# SCH_breakout_2024-04-23.net
KiCad netlist of a schematic drawn in EasyEDA
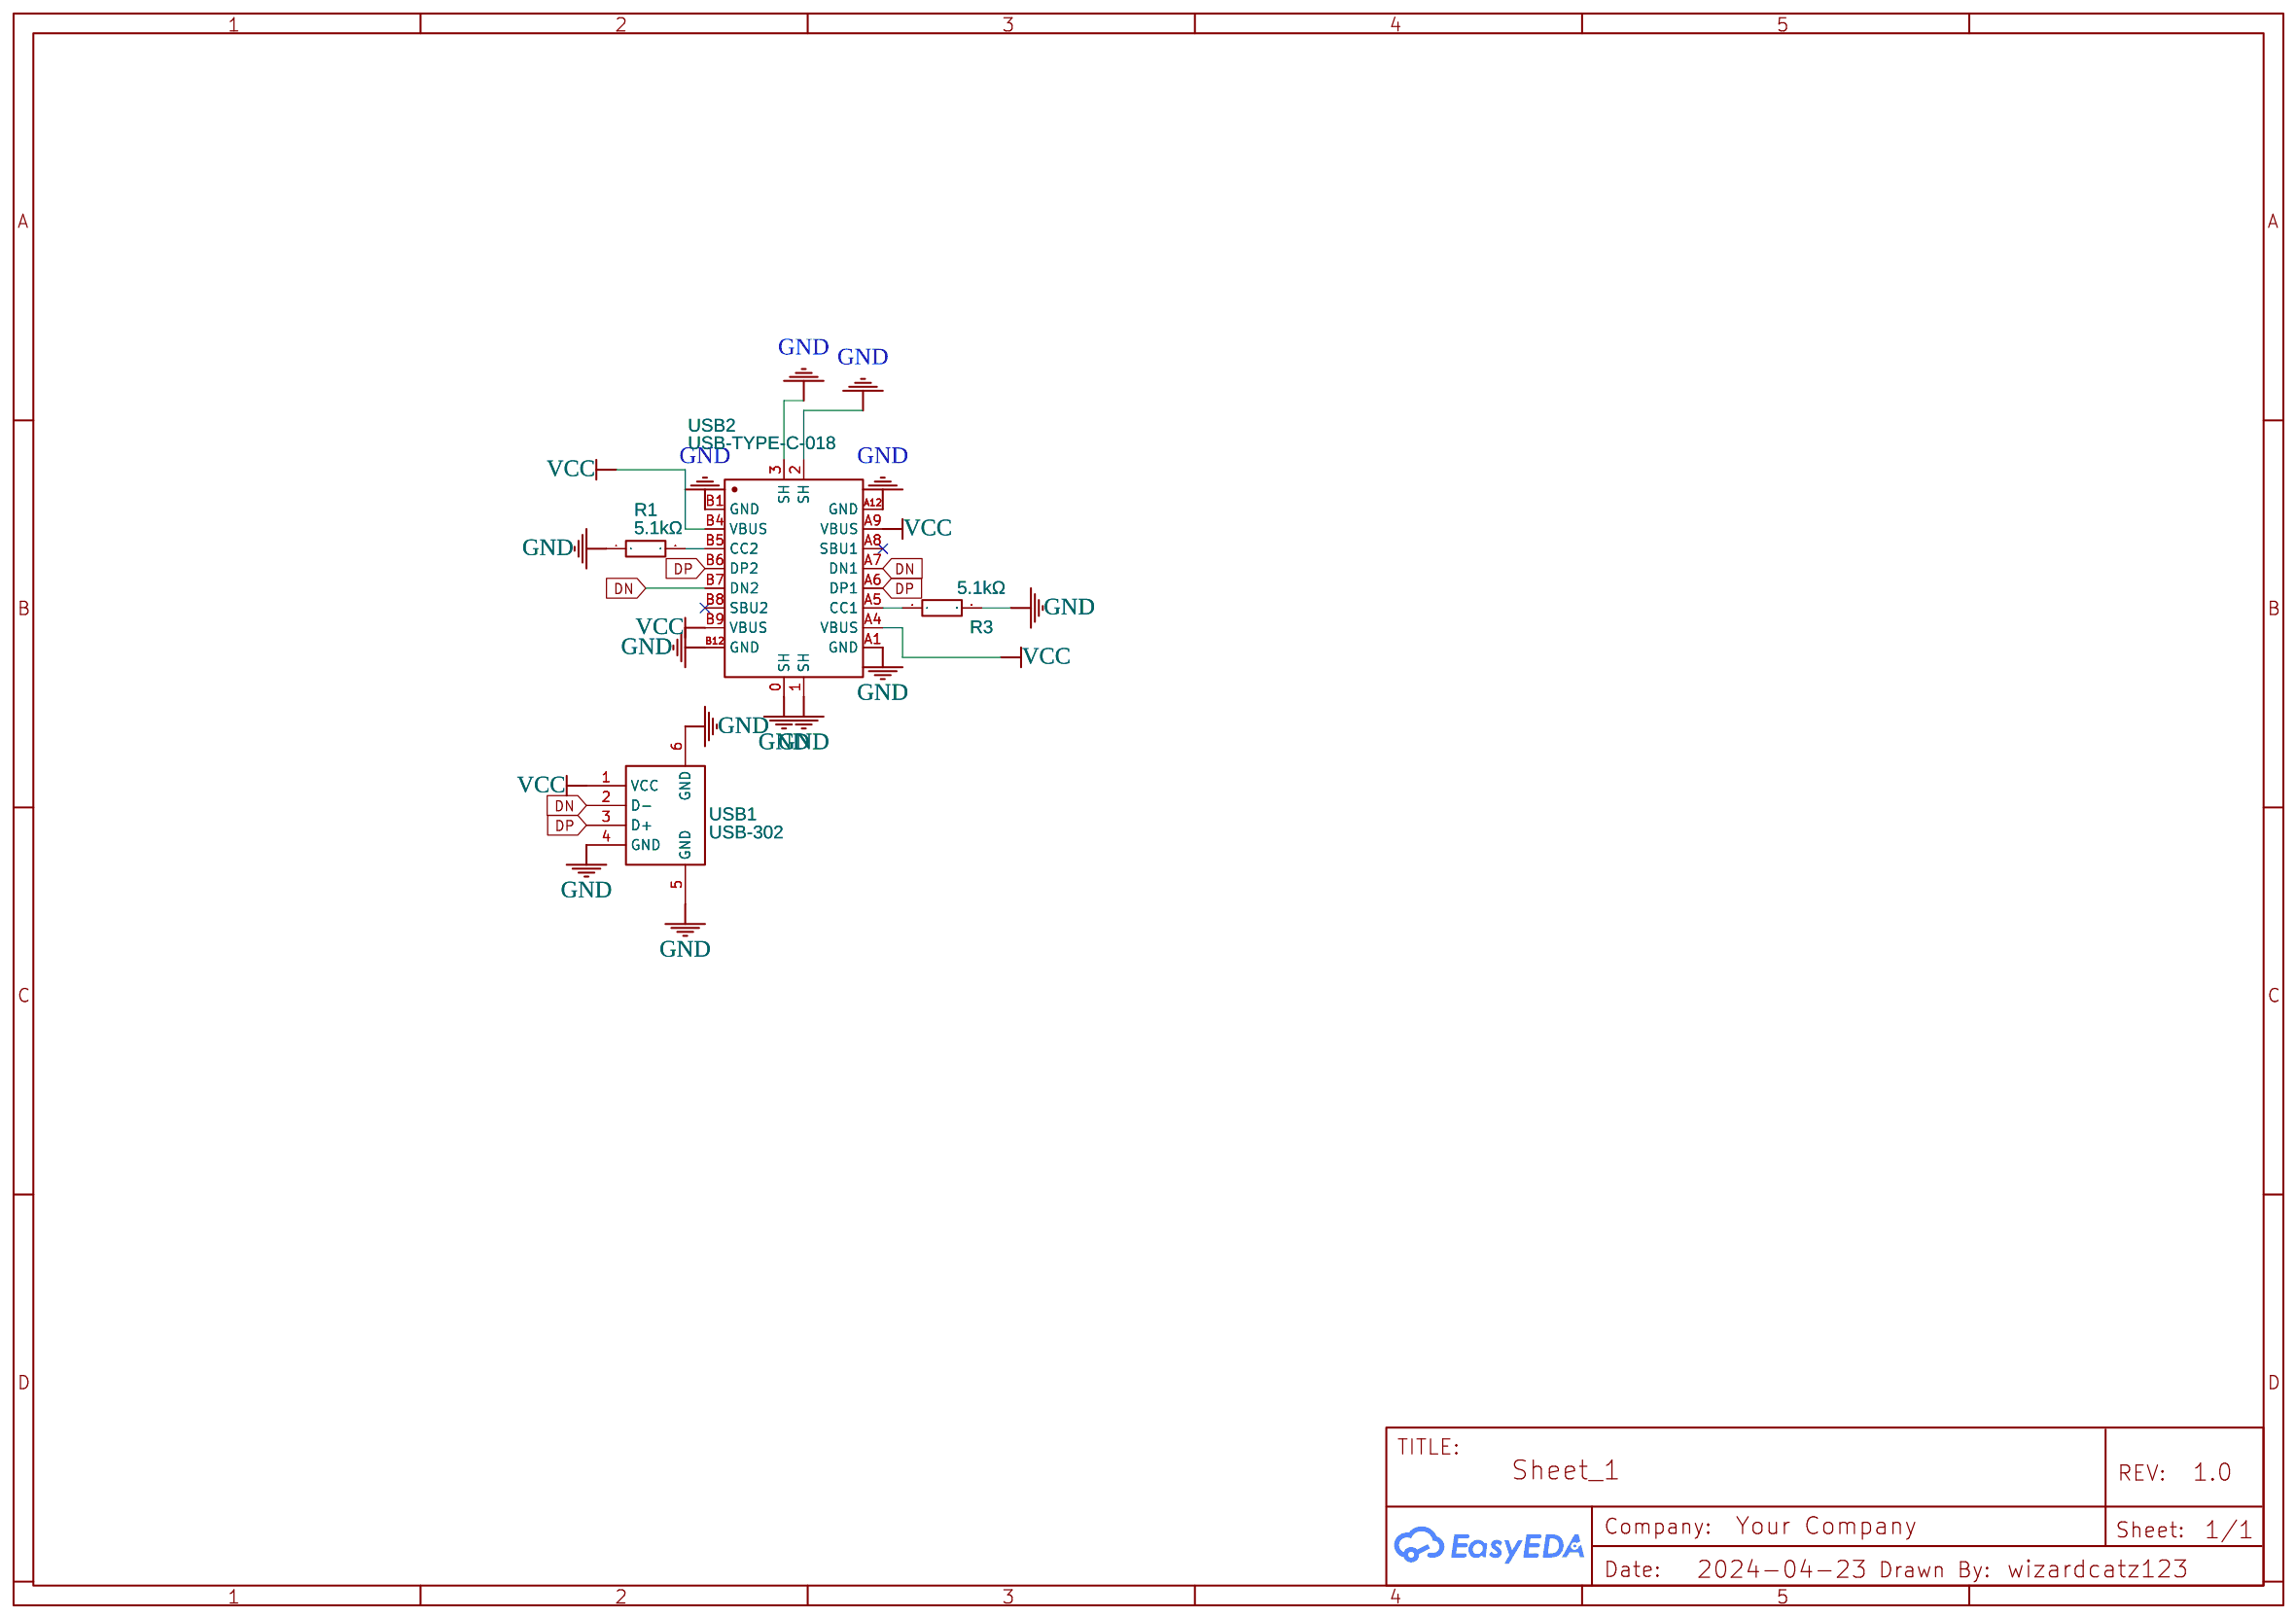
[diagram p0: schematic sheet]

(export (version "E")
  (design (tool "Eeschema 10.0.6"))
  (components
    (comp (ref "R1")
      (value "5.1kΩ")
      (fields (field (name "Manufacturer Part") "WR02X5101FALV") (field (name "Manufacturer") "Walsin(华新科)"))
      (libsource (lib "") (part "WR02X5101FALV"))
    )
    (comp (ref "R3")
      (value "5.1kΩ")
      (fields (field (name "Manufacturer Part") "WR02X5101FALV") (field (name "Manufacturer") "Walsin(华新科)"))
      (libsource (lib "") (part "WR02X5101FALV"))
    )
    (comp (ref "USB1")
      (value "USB-302")
      (fields (field (name "Manufacturer Part") "USB-302-T") (field (name "Manufacturer") "SOFNG(硕方)"))
      (libsource (lib "") (part "USB-302"))
    )
    (comp (ref "USB2")
      (value "USB-TYPE-C-018")
      (fields (field (name "Manufacturer") "DEALON(德艺隆)"))
      (libsource (lib "") (part "USB-TYPE-C-018"))
    )
  )
  (nets
    (net (code "1") (name "DN") (class "Default")
      (node (ref "USB1") (pin "2") (pinfunction "D-_2") (pintype "unspecified"))
      (node (ref "USB2") (pin "A7") (pinfunction "DN1_A7") (pintype "unspecified"))
      (node (ref "USB2") (pin "B7") (pinfunction "DN2_B7") (pintype "unspecified"))
    )
    (net (code "2") (name "DP") (class "Default")
      (node (ref "USB1") (pin "3") (pinfunction "D+_3") (pintype "unspecified"))
      (node (ref "USB2") (pin "A6") (pinfunction "DP1_A6") (pintype "unspecified"))
      (node (ref "USB2") (pin "B6") (pinfunction "DP2_B6") (pintype "unspecified"))
    )
    (net (code "3") (name "GND") (class "Default")
      (node (ref "R1") (pin "1") (pinfunction "1_1") (pintype "unspecified"))
      (node (ref "R3") (pin "2") (pinfunction "2_2") (pintype "unspecified"))
      (node (ref "USB1") (pin "4") (pinfunction "GND_4") (pintype "unspecified"))
      (node (ref "USB1") (pin "5") (pinfunction "GND_5") (pintype "unspecified"))
      (node (ref "USB1") (pin "6") (pinfunction "GND_6") (pintype "unspecified"))
      (node (ref "USB2") (pin "0") (pinfunction "SH_0") (pintype "unspecified"))
      (node (ref "USB2") (pin "1") (pinfunction "SH_1") (pintype "unspecified"))
      (node (ref "USB2") (pin "2") (pinfunction "SH_2") (pintype "unspecified"))
      (node (ref "USB2") (pin "3") (pinfunction "SH_3") (pintype "unspecified"))
      (node (ref "USB2") (pin "A1") (pinfunction "GND_A1") (pintype "unspecified"))
      (node (ref "USB2") (pin "A12") (pinfunction "GND_A12") (pintype "unspecified"))
      (node (ref "USB2") (pin "B1") (pinfunction "GND_B1") (pintype "unspecified"))
      (node (ref "USB2") (pin "B12") (pinfunction "GND_B12") (pintype "unspecified"))
    )
    (net (code "4") (name "Net-(USB2-CC1)") (class "Default")
      (node (ref "R3") (pin "1") (pinfunction "1_1") (pintype "unspecified"))
      (node (ref "USB2") (pin "A5") (pinfunction "CC1_A5") (pintype "unspecified"))
    )
    (net (code "5") (name "Net-(USB2-CC2)") (class "Default")
      (node (ref "R1") (pin "2") (pinfunction "2_2") (pintype "unspecified"))
      (node (ref "USB2") (pin "B5") (pinfunction "CC2_B5") (pintype "unspecified"))
    )
    (net (code "6") (name "VCC") (class "Default")
      (node (ref "USB1") (pin "1") (pinfunction "VCC_1") (pintype "unspecified"))
      (node (ref "USB2") (pin "A4") (pinfunction "VBUS_A4") (pintype "unspecified"))
      (node (ref "USB2") (pin "A9") (pinfunction "VBUS_A9") (pintype "unspecified"))
      (node (ref "USB2") (pin "B4") (pinfunction "VBUS_B4") (pintype "unspecified"))
      (node (ref "USB2") (pin "B9") (pinfunction "VBUS_B9") (pintype "unspecified"))
    )
    (net (code "7") (name "unconnected-(USB2-SBU1-PadA8)") (class "Default")
      (node (ref "USB2") (pin "A8") (pinfunction "SBU1_A8") (pintype "unspecified+no_connect"))
    )
    (net (code "8") (name "unconnected-(USB2-SBU2-PadB8)") (class "Default")
      (node (ref "USB2") (pin "B8") (pinfunction "SBU2_B8") (pintype "unspecified+no_connect"))
    )
  )
)
